# Adafruit_MOSFET_Driver_STEMMA_Breakout.net
KiCad netlist of a schematic drawn in EAGLE
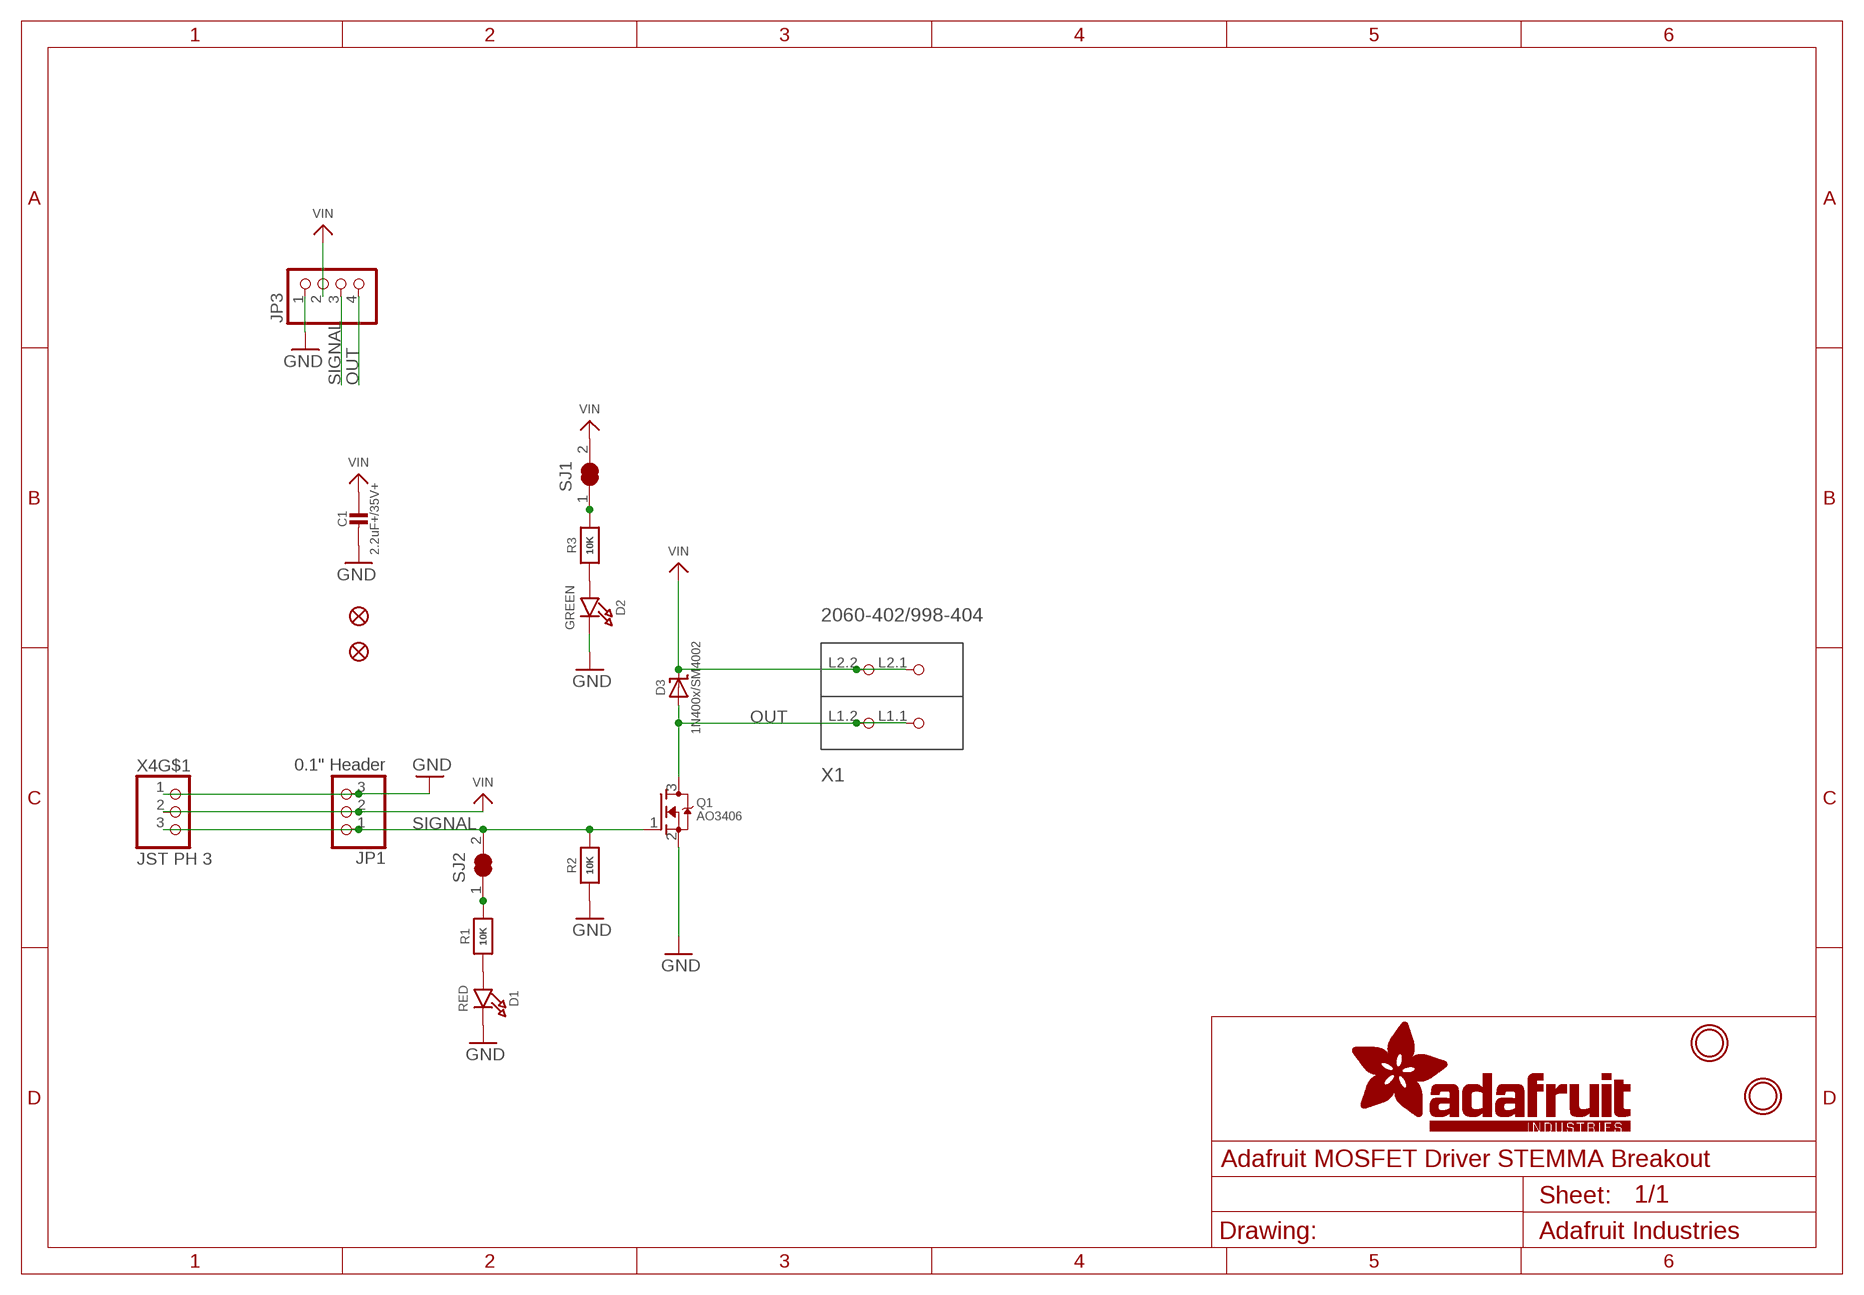
[diagram p0: schematic, sheet 1]

(export (version "E")
  (design (tool "Eeschema 10.0.6"))
  (components
    (comp (ref "C1")
      (value "2.2uF+/35V+")
      (footprint "eagle-import:0805-NO")
      (libsource (lib "eagle-import") (part "CAP_CERAMIC0805-NOOUTLINE"))
    )
    (comp (ref "D1")
      (value "RED")
      (footprint "eagle-import:CHIPLED_0603_NOOUTLINE")
      (libsource (lib "eagle-import") (part "LED0603_NOOUTLINE"))
    )
    (comp (ref "D2")
      (value "GREEN")
      (footprint "eagle-import:CHIPLED_0603_NOOUTLINE")
      (libsource (lib "eagle-import") (part "LED0603_NOOUTLINE"))
    )
    (comp (ref "D3")
      (value "1N400x/SM4002")
      (footprint "eagle-import:SOD-123")
      (libsource (lib "eagle-import") (part "DIODE-SCHOTTKYSOD-123"))
    )
    (comp (ref "FID2")
      (value "FIDUCIAL_1MM")
      (footprint "eagle-import:FIDUCIAL_1MM")
      (libsource (lib "eagle-import") (part "FIDUCIAL_1MM"))
    )
    (comp (ref "FID3")
      (value "FIDUCIAL_1MM")
      (footprint "eagle-import:FIDUCIAL_1MM")
      (libsource (lib "eagle-import") (part "FIDUCIAL_1MM"))
    )
    (comp (ref "JP1")
      (value "0.1\" Header")
      (footprint "eagle-import:1X03_OVAL")
      (libsource (lib "eagle-import") (part "HEADER-1X3"))
    )
    (comp (ref "JP3")
      (value "HEADER-1X4ROUND")
      (footprint "eagle-import:1X04_ROUND")
      (libsource (lib "eagle-import") (part "HEADER-1X4ROUND"))
    )
    (comp (ref "Q1")
      (value "AO3406")
      (footprint "eagle-import:SOT23-WIDE")
      (libsource (lib "eagle-import") (part "MOSFET-NWIDE"))
    )
    (comp (ref "R1")
      (value "10K")
      (footprint "eagle-import:0603-NO")
      (libsource (lib "eagle-import") (part "RESISTOR_0603_NOOUT"))
    )
    (comp (ref "R2")
      (value "10K")
      (footprint "eagle-import:0603-NO")
      (libsource (lib "eagle-import") (part "RESISTOR_0603_NOOUT"))
    )
    (comp (ref "R3")
      (value "10K")
      (footprint "eagle-import:0603-NO")
      (libsource (lib "eagle-import") (part "RESISTOR_0603_NOOUT"))
    )
    (comp (ref "SJ1")
      (value "SOLDERJUMPER_CLOSED")
      (footprint "eagle-import:SOLDERJUMPER_CLOSEDWIRE")
      (libsource (lib "eagle-import") (part "SOLDERJUMPER_CLOSED"))
    )
    (comp (ref "SJ2")
      (value "SOLDERJUMPER_CLOSED")
      (footprint "eagle-import:SOLDERJUMPER_CLOSEDWIRE")
      (libsource (lib "eagle-import") (part "SOLDERJUMPER_CLOSED"))
    )
    (comp (ref "U$1")
      (value "MOUNTINGHOLE2.5")
      (footprint "eagle-import:MOUNTINGHOLE_2.5_PLATED")
      (libsource (lib "eagle-import") (part "MOUNTINGHOLE2.5"))
    )
    (comp (ref "U$8")
      (value "MOUNTINGHOLE2.5")
      (footprint "eagle-import:MOUNTINGHOLE_2.5_PLATED")
      (libsource (lib "eagle-import") (part "MOUNTINGHOLE2.5"))
    )
    (comp (ref "X1")
      (value "2060-402/998-404")
      (footprint "eagle-import:P-2060-402_998-404")
      (libsource (lib "eagle-import") (part "2060-402/998-404"))
    )
    (comp (ref "X4")
      (value "JST PH 3")
      (footprint "eagle-import:JSTPH3")
      (libsource (lib "eagle-import") (part "CON_JST_PH_3PIN"))
    )
  )
  (nets
    (net (code "1") (name "/OUT") (class "Default")
      (node (ref "D3") (pin "A") (pinfunction "A_A") (pintype "passive"))
      (node (ref "JP3") (pin "4") (pinfunction "4_4") (pintype "passive"))
      (node (ref "Q1") (pin "3") (pinfunction "D_3") (pintype "bidirectional"))
      (node (ref "X1") (pin "L1.1") (pinfunction "P1.1_L1.1") (pintype "bidirectional"))
      (node (ref "X1") (pin "L1.2") (pinfunction "P1.2_L1.2") (pintype "bidirectional"))
    )
    (net (code "2") (name "/SIGNAL") (class "Default")
      (node (ref "JP1") (pin "1") (pinfunction "1_1") (pintype "passive"))
      (node (ref "JP3") (pin "3") (pinfunction "3_3") (pintype "passive"))
      (node (ref "Q1") (pin "1") (pinfunction "G_1") (pintype "bidirectional"))
      (node (ref "R2") (pin "2") (pinfunction "2_2") (pintype "passive"))
      (node (ref "SJ2") (pin "2") (pinfunction "2_2") (pintype "passive"))
      (node (ref "X4") (pin "3") (pinfunction "3_3") (pintype "passive"))
    )
    (net (code "3") (name "GND") (class "Default")
      (node (ref "C1") (pin "2") (pinfunction "2_2") (pintype "passive"))
      (node (ref "D1") (pin "C") (pinfunction "C_C") (pintype "passive"))
      (node (ref "D2") (pin "C") (pinfunction "C_C") (pintype "passive"))
      (node (ref "JP1") (pin "3") (pinfunction "3_3") (pintype "passive"))
      (node (ref "JP3") (pin "1") (pinfunction "1_1") (pintype "passive"))
      (node (ref "Q1") (pin "2") (pinfunction "S_2") (pintype "bidirectional"))
      (node (ref "R2") (pin "1") (pinfunction "1_1") (pintype "passive"))
      (node (ref "X4") (pin "1") (pinfunction "1_1") (pintype "passive"))
    )
    (net (code "4") (name "Net-(D1-PadA)") (class "Default")
      (node (ref "D1") (pin "A") (pinfunction "A_A") (pintype "passive"))
      (node (ref "R1") (pin "1") (pinfunction "1_1") (pintype "passive"))
    )
    (net (code "5") (name "Net-(D2-PadA)") (class "Default")
      (node (ref "D2") (pin "A") (pinfunction "A_A") (pintype "passive"))
      (node (ref "R3") (pin "1") (pinfunction "1_1") (pintype "passive"))
    )
    (net (code "6") (name "Net-(R1-Pad2)") (class "Default")
      (node (ref "R1") (pin "2") (pinfunction "2_2") (pintype "passive"))
      (node (ref "SJ2") (pin "1") (pinfunction "1_1") (pintype "passive"))
    )
    (net (code "7") (name "Net-(R3-Pad2)") (class "Default")
      (node (ref "R3") (pin "2") (pinfunction "2_2") (pintype "passive"))
      (node (ref "SJ1") (pin "1") (pinfunction "1_1") (pintype "passive"))
    )
    (net (code "8") (name "VIN") (class "Default")
      (node (ref "C1") (pin "1") (pinfunction "1_1") (pintype "passive"))
      (node (ref "D3") (pin "C") (pinfunction "C_C") (pintype "passive"))
      (node (ref "JP1") (pin "2") (pinfunction "2_2") (pintype "passive"))
      (node (ref "JP3") (pin "2") (pinfunction "2_2") (pintype "passive"))
      (node (ref "SJ1") (pin "2") (pinfunction "2_2") (pintype "passive"))
      (node (ref "X1") (pin "L2.1") (pinfunction "P2.1_L2.1") (pintype "bidirectional"))
      (node (ref "X1") (pin "L2.2") (pinfunction "P2.2_L2.2") (pintype "bidirectional"))
      (node (ref "X4") (pin "2") (pinfunction "2_2") (pintype "passive"))
    )
  )
)
